# finger_jlink_r1_3.net
KiCad netlist of a schematic drawn in EAGLE
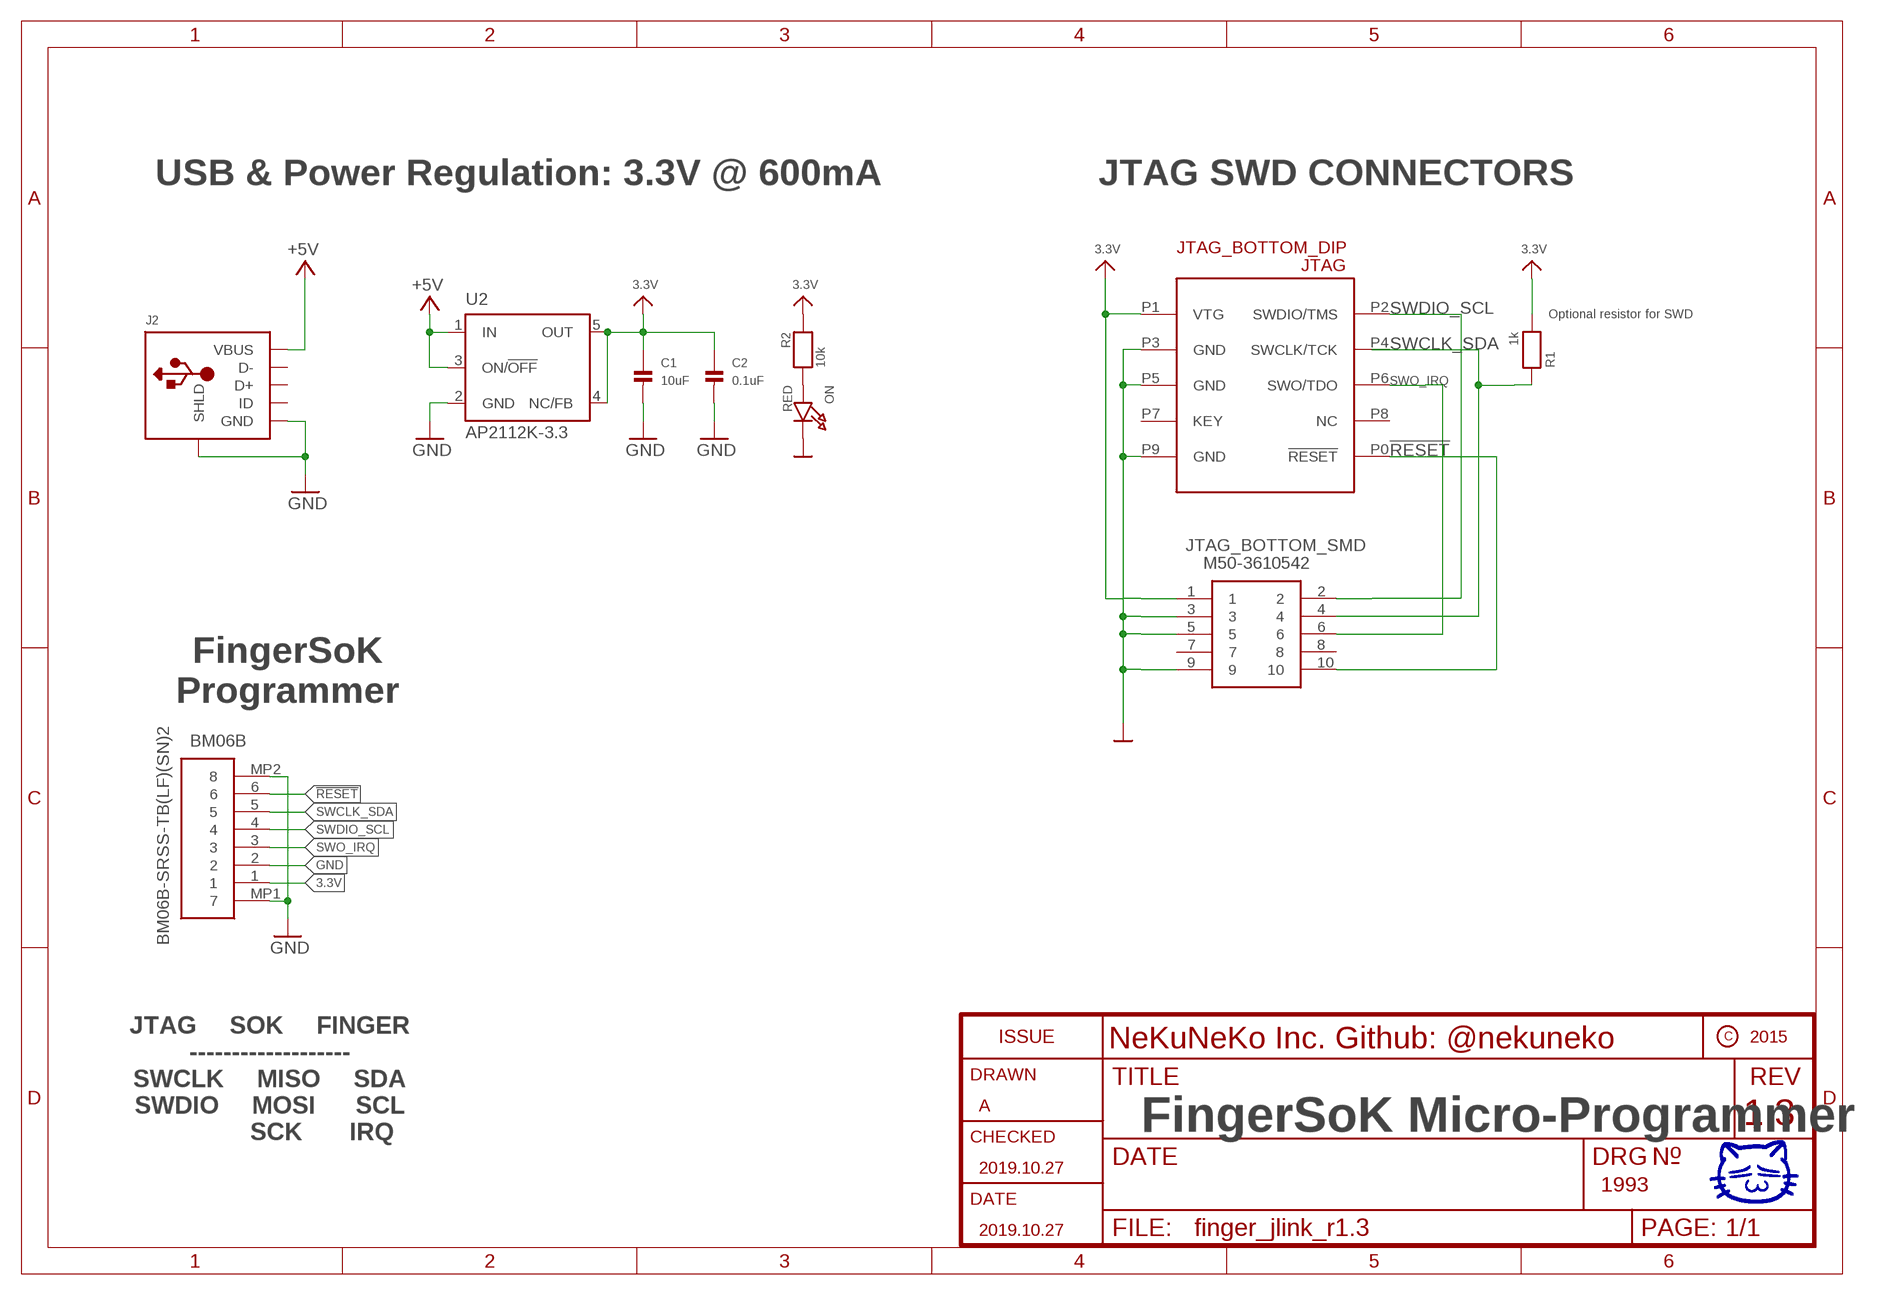
[diagram p0: schematic, sheet 1]

(export (version "E")
  (design (tool "Eeschema 10.0.6"))
  (components
    (comp (ref "BM06B")
      (value "BM06B-SRSS-TB(LF)(SN)2")
      (footprint "eagle-import:BM06B-SRSS-TB(LF)(SN)_2")
      (libsource (lib "eagle-import") (part "BM06B-SRSS-TB(LF)(SN)2"))
    )
    (comp (ref "C1")
      (value "10uF")
      (footprint "eagle-import:_0402")
      (libsource (lib "eagle-import") (part "CAP_CERAMIC_0402"))
    )
    (comp (ref "C2")
      (value "0.1uF")
      (footprint "eagle-import:_0402")
      (libsource (lib "eagle-import") (part "CAP_CERAMIC_0402"))
    )
    (comp (ref "J2")
      (value "FLAT_MICROUSB_ALIEXPRESS_TYPE_4")
      (footprint "eagle-import:USB_TYPE_4_105164-0001")
      (libsource (lib "eagle-import") (part "FLAT_MICROUSB_ALIEXPRESS_TYPE_4"))
    )
    (comp (ref "JTAG_BOTTOM_DIP")
      (value "JTAGICE3-CONNECTOR50MIL-THT")
      (footprint "eagle-import:JTAGICE3-50MIL")
      (libsource (lib "eagle-import") (part "JTAGICE3-CONNECTOR50MIL-THT"))
    )
    (comp (ref "JTAG_BOTTOM_SMD")
      (value "M50-3610542")
      (footprint "eagle-import:M503610542")
      (fields (field (name "MOUSER_PART_NUMBER") "855-M50-3610542"))
      (libsource (lib "eagle-import") (part "M50-3610542"))
    )
    (comp (ref "ON")
      (value "RED")
      (footprint "eagle-import:CHIPLED_0603")
      (libsource (lib "eagle-import") (part "LED0603"))
    )
    (comp (ref "R1")
      (value "1k")
      (footprint "eagle-import:_0402")
      (libsource (lib "eagle-import") (part "RESISTOR_0402"))
    )
    (comp (ref "R2")
      (value "10k")
      (footprint "eagle-import:_0402")
      (libsource (lib "eagle-import") (part "RESISTOR_0402"))
    )
    (comp (ref "U2")
      (value "AP2112K-3.3")
      (footprint "eagle-import:SOT23-DBV")
      (libsource (lib "eagle-import") (part "LP2985-XXDBVR33"))
    )
  )
  (nets
    (net (code "1") (name "+5V") (class "Default")
      (node (ref "J2") (pin "P$5") (pinfunction "VBUS_P$5") (pintype "power_in"))
      (node (ref "U2") (pin "1") (pinfunction "IN_1") (pintype "input"))
      (node (ref "U2") (pin "3") (pinfunction "ON/~{OFF}_3") (pintype "input"))
    )
    (net (code "2") (name "/~{RESET}") (class "Default")
      (node (ref "BM06B") (pin "6") (pinfunction "6_6") (pintype "bidirectional"))
      (node (ref "JTAG_BOTTOM_DIP") (pin "P0") (pinfunction "~{RESET}_P0") (pintype "bidirectional"))
      (node (ref "JTAG_BOTTOM_SMD") (pin "10") (pinfunction "10_10") (pintype "bidirectional"))
    )
    (net (code "3") (name "3.3V") (class "Default")
      (node (ref "BM06B") (pin "1") (pinfunction "1_1") (pintype "bidirectional"))
      (node (ref "C1") (pin "1") (pinfunction "P$1_1") (pintype "passive"))
      (node (ref "C2") (pin "1") (pinfunction "P$1_1") (pintype "passive"))
      (node (ref "JTAG_BOTTOM_DIP") (pin "P1") (pinfunction "VTG_P1") (pintype "bidirectional"))
      (node (ref "JTAG_BOTTOM_SMD") (pin "1") (pinfunction "1_1") (pintype "bidirectional"))
      (node (ref "R1") (pin "2") (pinfunction "2_2") (pintype "passive"))
      (node (ref "R2") (pin "2") (pinfunction "2_2") (pintype "passive"))
      (node (ref "U2") (pin "4") (pinfunction "NC/FB_4") (pintype "passive"))
      (node (ref "U2") (pin "5") (pinfunction "OUT_5") (pintype "passive"))
    )
    (net (code "4") (name "GND") (class "Default")
      (node (ref "BM06B") (pin "2") (pinfunction "2_2") (pintype "bidirectional"))
      (node (ref "BM06B") (pin "MP1") (pinfunction "7_MP1") (pintype "bidirectional"))
      (node (ref "BM06B") (pin "MP2") (pinfunction "8_MP2") (pintype "bidirectional"))
      (node (ref "C1") (pin "2") (pinfunction "P$2_2") (pintype "passive"))
      (node (ref "C2") (pin "2") (pinfunction "P$2_2") (pintype "passive"))
      (node (ref "J2") (pin "P$1") (pinfunction "GND_P$1") (pintype "power_in"))
      (node (ref "J2") (pin "P$8") (pinfunction "SHLD_P$8") (pintype "power_in"))
      (node (ref "J2") (pin "P$9") (pinfunction "SHLD_P$9") (pintype "power_in"))
      (node (ref "JTAG_BOTTOM_DIP") (pin "P3") (pinfunction "GND_P3") (pintype "bidirectional"))
      (node (ref "JTAG_BOTTOM_DIP") (pin "P5") (pinfunction "GND_P5") (pintype "bidirectional"))
      (node (ref "JTAG_BOTTOM_DIP") (pin "P9") (pinfunction "GND_P9") (pintype "bidirectional"))
      (node (ref "JTAG_BOTTOM_SMD") (pin "3") (pinfunction "3_3") (pintype "bidirectional"))
      (node (ref "JTAG_BOTTOM_SMD") (pin "5") (pinfunction "5_5") (pintype "bidirectional"))
      (node (ref "JTAG_BOTTOM_SMD") (pin "9") (pinfunction "9_9") (pintype "bidirectional"))
      (node (ref "ON") (pin "C") (pinfunction "C_C") (pintype "passive"))
      (node (ref "U2") (pin "2") (pinfunction "GND_2") (pintype "power_in"))
    )
    (net (code "5") (name "Net-(ON-PadA)") (class "Default")
      (node (ref "ON") (pin "A") (pinfunction "A_A") (pintype "passive"))
      (node (ref "R2") (pin "1") (pinfunction "1_1") (pintype "passive"))
    )
    (net (code "6") (name "SWCLK_SDA") (class "Default")
      (node (ref "BM06B") (pin "5") (pinfunction "5_5") (pintype "bidirectional"))
      (node (ref "JTAG_BOTTOM_DIP") (pin "P4") (pinfunction "SWCLK/TCK_P4") (pintype "bidirectional"))
      (node (ref "JTAG_BOTTOM_SMD") (pin "4") (pinfunction "4_4") (pintype "bidirectional"))
      (node (ref "R1") (pin "1") (pinfunction "1_1") (pintype "passive"))
    )
    (net (code "7") (name "SWDIO_SCL") (class "Default")
      (node (ref "BM06B") (pin "4") (pinfunction "4_4") (pintype "bidirectional"))
      (node (ref "JTAG_BOTTOM_DIP") (pin "P2") (pinfunction "SWDIO/TMS_P2") (pintype "bidirectional"))
      (node (ref "JTAG_BOTTOM_SMD") (pin "2") (pinfunction "2_2") (pintype "bidirectional"))
    )
    (net (code "8") (name "SWO_IRQ") (class "Default")
      (node (ref "BM06B") (pin "3") (pinfunction "3_3") (pintype "bidirectional"))
      (node (ref "JTAG_BOTTOM_DIP") (pin "P6") (pinfunction "SWO/TDO_P6") (pintype "bidirectional"))
      (node (ref "JTAG_BOTTOM_SMD") (pin "6") (pinfunction "6_6") (pintype "bidirectional"))
    )
    (net (code "9") (name "unconnected-(J2-D+-PadP$3)") (class "Default")
      (node (ref "J2") (pin "P$3") (pinfunction "D+_P$3") (pintype "bidirectional"))
    )
    (net (code "10") (name "unconnected-(J2-D--PadP$4)") (class "Default")
      (node (ref "J2") (pin "P$4") (pinfunction "D-_P$4") (pintype "bidirectional"))
    )
    (net (code "11") (name "unconnected-(J2-ID-PadP$2)") (class "Default")
      (node (ref "J2") (pin "P$2") (pinfunction "ID_P$2") (pintype "bidirectional"))
    )
    (net (code "12") (name "unconnected-(JTAG_BOTTOM_DIP-KEY-PadP7)") (class "Default")
      (node (ref "JTAG_BOTTOM_DIP") (pin "P7") (pinfunction "KEY_P7") (pintype "bidirectional"))
    )
    (net (code "13") (name "unconnected-(JTAG_BOTTOM_DIP-NC-PadP8)") (class "Default")
      (node (ref "JTAG_BOTTOM_DIP") (pin "P8") (pinfunction "NC_P8") (pintype "bidirectional"))
    )
    (net (code "14") (name "unconnected-(JTAG_BOTTOM_SMD-Pad7)") (class "Default")
      (node (ref "JTAG_BOTTOM_SMD") (pin "7") (pinfunction "7_7") (pintype "bidirectional"))
    )
    (net (code "15") (name "unconnected-(JTAG_BOTTOM_SMD-Pad8)") (class "Default")
      (node (ref "JTAG_BOTTOM_SMD") (pin "8") (pinfunction "8_8") (pintype "bidirectional"))
    )
  )
)
